# Venus_GPS_logger-sma.net
KiCad netlist of a schematic drawn in EAGLE
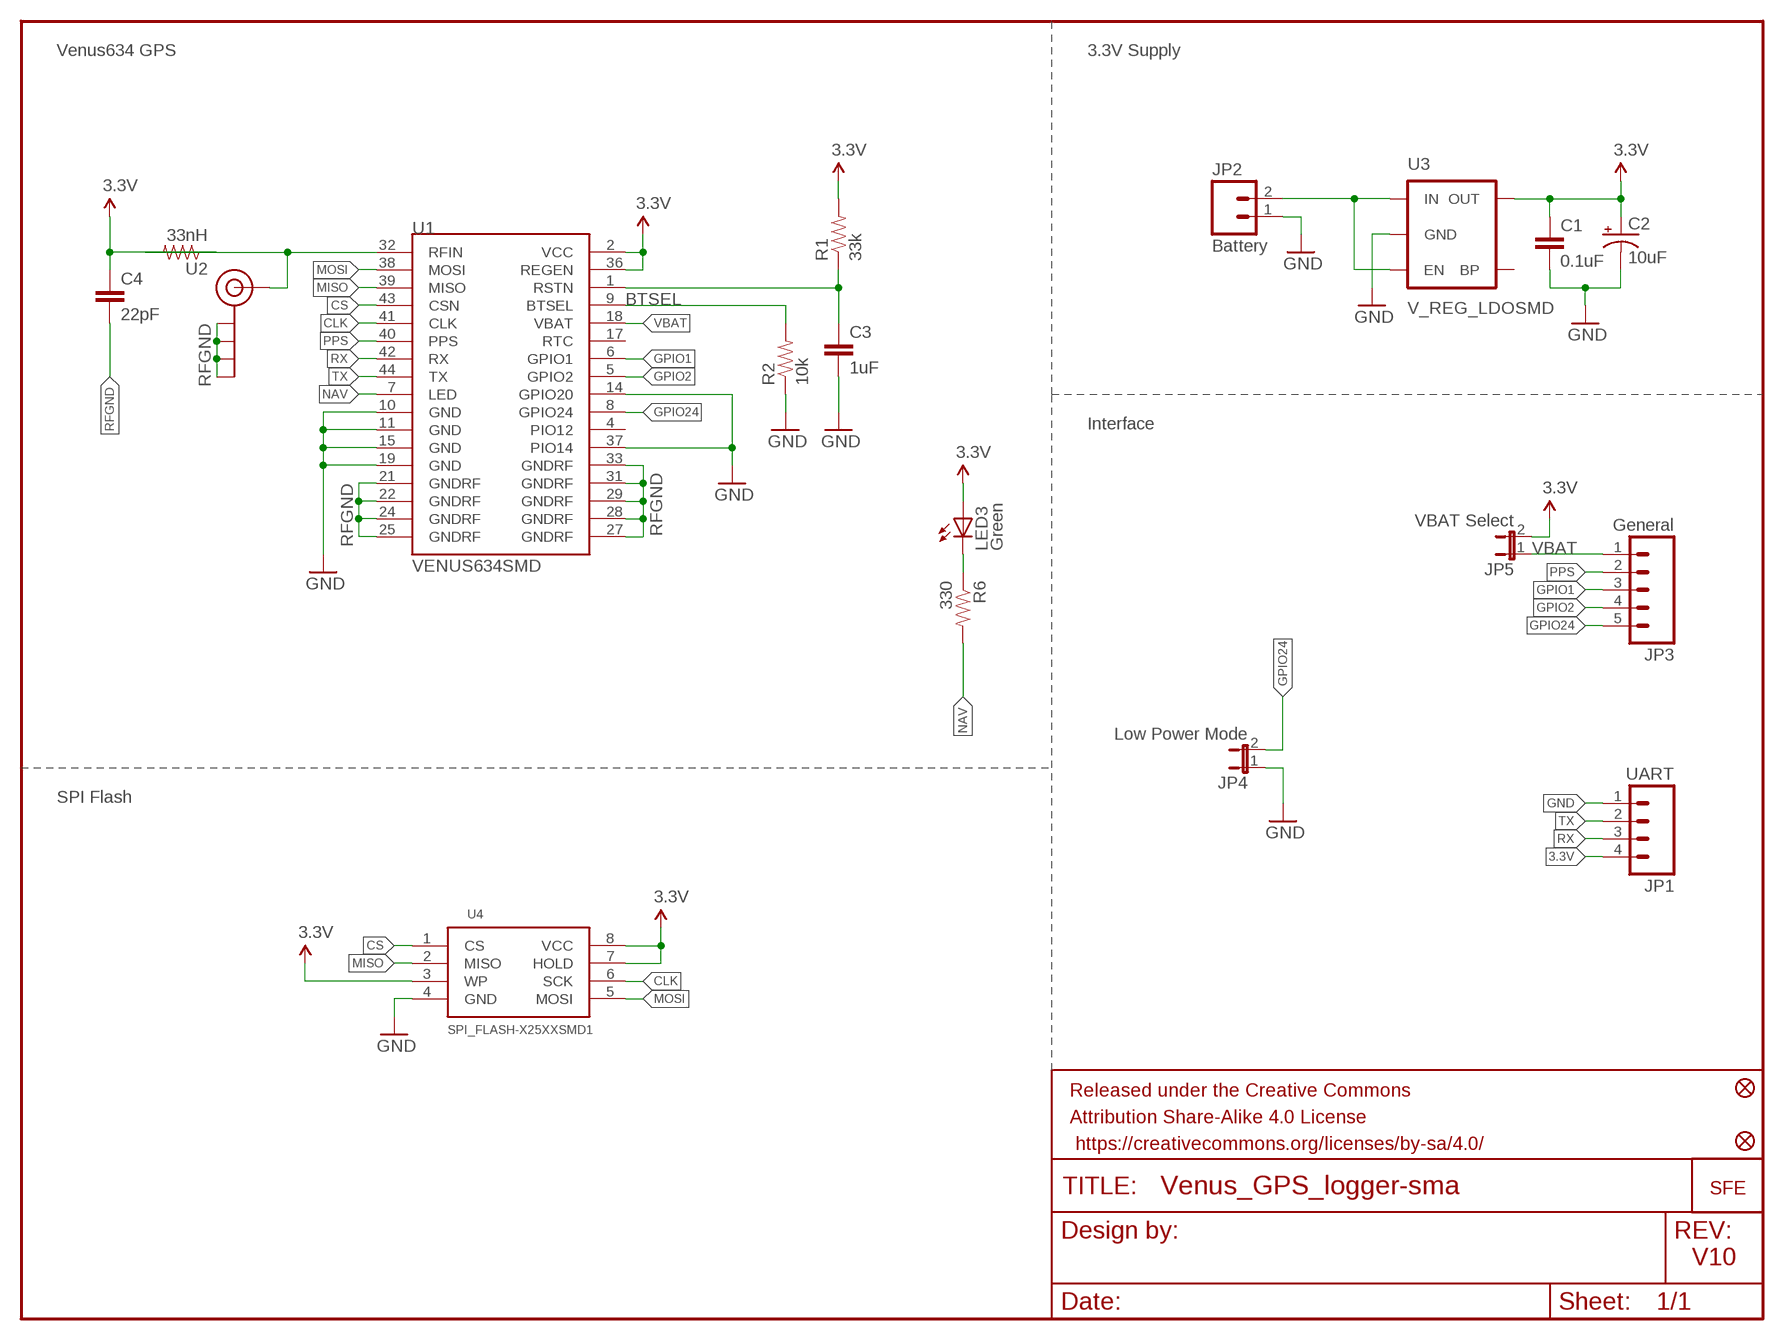
[diagram p0: schematic, sheet 1]

(export (version "E")
  (design (tool "Eeschema 10.0.6"))
  (components
    (comp (ref "C1")
      (value "0.1uF")
      (footprint "eagle-import:0603-CAP")
      (libsource (lib "eagle-import") (part "0.1UF-25V(+80/-20%)(0603)"))
    )
    (comp (ref "C2")
      (value "10uF")
      (footprint "eagle-import:EIA3216")
      (libsource (lib "eagle-import") (part "CAP_POL1206"))
    )
    (comp (ref "C3")
      (value "1uF")
      (footprint "eagle-import:0603-CAP")
      (libsource (lib "eagle-import") (part "1.0UF-16V-10%(0603)"))
    )
    (comp (ref "C4")
      (value "22pF")
      (footprint "eagle-import:0603-CAP")
      (libsource (lib "eagle-import") (part "22PF-50V-5%(0603)"))
    )
    (comp (ref "FID1")
      (value "FIDUCIAL1X2")
      (footprint "eagle-import:FIDUCIAL-1X2")
      (libsource (lib "eagle-import") (part "FIDUCIAL1X2"))
    )
    (comp (ref "FID2")
      (value "FIDUCIAL1X2")
      (footprint "eagle-import:FIDUCIAL-1X2")
      (libsource (lib "eagle-import") (part "FIDUCIAL1X2"))
    )
    (comp (ref "FRAME1")
      (value "FRAME-LETTER")
      (footprint "eagle-import:CREATIVE_COMMONS")
      (libsource (lib "eagle-import") (part "FRAME-LETTER"))
    )
    (comp (ref "J$1")
      (value "SMA_EDGE")
      (footprint "eagle-import:SMA-EDGE")
      (libsource (lib "eagle-import") (part "SMA_EDGE"))
    )
    (comp (ref "JP1")
      (value "UART")
      (footprint "eagle-import:1X04")
      (libsource (lib "eagle-import") (part "M04PTH"))
    )
    (comp (ref "JP2")
      (value "Battery")
      (footprint "eagle-import:S2B-PH")
      (libsource (lib "eagle-import") (part "M02-JST-2MM-SMT"))
    )
    (comp (ref "JP3")
      (value "General")
      (footprint "eagle-import:1X05")
      (libsource (lib "eagle-import") (part "M05PTH"))
    )
    (comp (ref "JP4")
      (value "Low Power Mode")
      (footprint "eagle-import:SJ_2S")
      (libsource (lib "eagle-import") (part "JUMPER-2SMD-NC"))
    )
    (comp (ref "JP5")
      (value "VBAT Select")
      (footprint "eagle-import:SJ_2S")
      (libsource (lib "eagle-import") (part "JUMPER-2SMD-NC"))
    )
    (comp (ref "LED3")
      (value "Green")
      (footprint "eagle-import:LED-0603")
      (libsource (lib "eagle-import") (part "LED-GREEN0603"))
    )
    (comp (ref "R1")
      (value "33k")
      (footprint "eagle-import:0603-RES")
      (libsource (lib "eagle-import") (part "33KOHM1/10W1%(0603)"))
    )
    (comp (ref "R2")
      (value "10k")
      (footprint "eagle-import:0603-RES")
      (libsource (lib "eagle-import") (part "10KOHM1/10W1%(0603)0603"))
    )
    (comp (ref "R6")
      (value "330")
      (footprint "eagle-import:0603-RES")
      (libsource (lib "eagle-import") (part "330OHM1/10W1%(0603)"))
    )
    (comp (ref "U$1")
      (value "LOGO-SFESK")
      (footprint "eagle-import:SFE-LOGO-FLAME")
      (libsource (lib "eagle-import") (part "LOGO-SFESK"))
    )
    (comp (ref "U1")
      (value "VENUS634SMD")
      (footprint "eagle-import:LGA44")
      (libsource (lib "eagle-import") (part "VENUS634SMD"))
    )
    (comp (ref "U2")
      (value "33nH")
      (footprint "eagle-import:0603-RES")
      (libsource (lib "eagle-import") (part "33NH"))
    )
    (comp (ref "U3")
      (value "V_REG_LDOSMD")
      (footprint "eagle-import:SOT23-5")
      (libsource (lib "eagle-import") (part "V_REG_LDOSMD"))
    )
    (comp (ref "U4")
      (value "SPI_FLASH-X25XXSMD1")
      (footprint "eagle-import:SO08-EIAJ")
      (libsource (lib "eagle-import") (part "SPI_FLASH-X25XXSMD1"))
    )
  )
  (nets
    (net (code "1") (name "/BTSEL") (class "Default")
      (node (ref "R2") (pin "2") (pinfunction "2_2") (pintype "passive"))
      (node (ref "U1") (pin "9") (pinfunction "BTSEL_9") (pintype "bidirectional"))
    )
    (net (code "2") (name "3.3V") (class "Default")
      (node (ref "C1") (pin "1") (pinfunction "1_1") (pintype "passive"))
      (node (ref "C2") (pin "A") (pinfunction "+_A") (pintype "passive"))
      (node (ref "C4") (pin "1") (pinfunction "1_1") (pintype "passive"))
      (node (ref "JP1") (pin "4") (pinfunction "4_4") (pintype "passive"))
      (node (ref "JP5") (pin "2") (pinfunction "2_2") (pintype "passive"))
      (node (ref "LED3") (pin "A") (pinfunction "A_A") (pintype "passive"))
      (node (ref "R1") (pin "2") (pinfunction "2_2") (pintype "passive"))
      (node (ref "U1") (pin "2") (pinfunction "VCC_2") (pintype "bidirectional"))
      (node (ref "U1") (pin "36") (pinfunction "REGEN_36") (pintype "bidirectional"))
      (node (ref "U2") (pin "1") (pinfunction "1_1") (pintype "passive"))
      (node (ref "U3") (pin "5") (pinfunction "OUT_5") (pintype "passive"))
      (node (ref "U4") (pin "3") (pinfunction "WP_3") (pintype "bidirectional"))
      (node (ref "U4") (pin "7") (pinfunction "HOLD_7") (pintype "bidirectional"))
      (node (ref "U4") (pin "8") (pinfunction "VCC_8") (pintype "bidirectional"))
    )
    (net (code "3") (name "CLK") (class "Default")
      (node (ref "U1") (pin "41") (pinfunction "CLK_41") (pintype "bidirectional"))
      (node (ref "U4") (pin "6") (pinfunction "SCK_6") (pintype "bidirectional"))
    )
    (net (code "4") (name "CS") (class "Default")
      (node (ref "U1") (pin "43") (pinfunction "CSN_43") (pintype "bidirectional"))
      (node (ref "U4") (pin "1") (pinfunction "CS_1") (pintype "bidirectional"))
    )
    (net (code "5") (name "GND") (class "Default")
      (node (ref "C1") (pin "2") (pinfunction "2_2") (pintype "passive"))
      (node (ref "C2") (pin "C") (pinfunction "-_C") (pintype "passive"))
      (node (ref "C3") (pin "2") (pinfunction "2_2") (pintype "passive"))
      (node (ref "JP1") (pin "1") (pinfunction "1_1") (pintype "passive"))
      (node (ref "JP2") (pin "1") (pinfunction "1_1") (pintype "passive"))
      (node (ref "JP4") (pin "1") (pinfunction "1_1") (pintype "passive"))
      (node (ref "R2") (pin "1") (pinfunction "1_1") (pintype "passive"))
      (node (ref "U1") (pin "10") (pinfunction "GND_10") (pintype "bidirectional"))
      (node (ref "U1") (pin "11") (pinfunction "GND_11") (pintype "bidirectional"))
      (node (ref "U1") (pin "14") (pinfunction "GPIO20_14") (pintype "bidirectional"))
      (node (ref "U1") (pin "15") (pinfunction "GND_15") (pintype "bidirectional"))
      (node (ref "U1") (pin "19") (pinfunction "GND_19") (pintype "bidirectional"))
      (node (ref "U1") (pin "37") (pinfunction "PIO14_37") (pintype "bidirectional"))
      (node (ref "U3") (pin "2") (pinfunction "GND_2") (pintype "input"))
      (node (ref "U4") (pin "4") (pinfunction "GND_4") (pintype "bidirectional"))
    )
    (net (code "6") (name "GPIO1") (class "Default")
      (node (ref "JP3") (pin "3") (pinfunction "3_3") (pintype "passive"))
      (node (ref "U1") (pin "6") (pinfunction "GPIO1_6") (pintype "bidirectional"))
    )
    (net (code "7") (name "GPIO2") (class "Default")
      (node (ref "JP3") (pin "4") (pinfunction "4_4") (pintype "passive"))
      (node (ref "U1") (pin "5") (pinfunction "GPIO2_5") (pintype "bidirectional"))
    )
    (net (code "8") (name "GPIO24") (class "Default")
      (node (ref "JP3") (pin "5") (pinfunction "5_5") (pintype "passive"))
      (node (ref "JP4") (pin "2") (pinfunction "2_2") (pintype "passive"))
      (node (ref "U1") (pin "8") (pinfunction "GPIO24_8") (pintype "bidirectional"))
    )
    (net (code "9") (name "MISO") (class "Default")
      (node (ref "U1") (pin "39") (pinfunction "MISO_39") (pintype "bidirectional"))
      (node (ref "U4") (pin "2") (pinfunction "MISO_2") (pintype "bidirectional"))
    )
    (net (code "10") (name "MOSI") (class "Default")
      (node (ref "U1") (pin "38") (pinfunction "MOSI_38") (pintype "bidirectional"))
      (node (ref "U4") (pin "5") (pinfunction "MOSI_5") (pintype "bidirectional"))
    )
    (net (code "11") (name "NAV") (class "Default")
      (node (ref "R6") (pin "2") (pinfunction "2_2") (pintype "passive"))
      (node (ref "U1") (pin "7") (pinfunction "LED_7") (pintype "bidirectional"))
    )
    (net (code "12") (name "Net-(J$1-SIGNAL)") (class "Default")
      (node (ref "J$1") (pin "SIG") (pinfunction "SIGNAL_SIG") (pintype "bidirectional"))
      (node (ref "U1") (pin "32") (pinfunction "RFIN_32") (pintype "bidirectional"))
      (node (ref "U2") (pin "2") (pinfunction "2_2") (pintype "passive"))
    )
    (net (code "13") (name "Net-(LED3-PadC)") (class "Default")
      (node (ref "LED3") (pin "C") (pinfunction "C_C") (pintype "passive"))
      (node (ref "R6") (pin "1") (pinfunction "1_1") (pintype "passive"))
    )
    (net (code "14") (name "Net-(U1-RSTN)") (class "Default")
      (node (ref "C3") (pin "1") (pinfunction "1_1") (pintype "passive"))
      (node (ref "R1") (pin "1") (pinfunction "1_1") (pintype "passive"))
      (node (ref "U1") (pin "1") (pinfunction "RSTN_1") (pintype "bidirectional"))
    )
    (net (code "15") (name "Net-(U3-EN)") (class "Default")
      (node (ref "JP2") (pin "2") (pinfunction "2_2") (pintype "passive"))
      (node (ref "U3") (pin "1") (pinfunction "IN_1") (pintype "input"))
      (node (ref "U3") (pin "3") (pinfunction "EN_3") (pintype "input"))
    )
    (net (code "16") (name "PPS") (class "Default")
      (node (ref "JP3") (pin "2") (pinfunction "2_2") (pintype "passive"))
      (node (ref "U1") (pin "40") (pinfunction "PPS_40") (pintype "bidirectional"))
    )
    (net (code "17") (name "RFGND") (class "Default")
      (node (ref "C4") (pin "2") (pinfunction "2_2") (pintype "passive"))
      (node (ref "J$1") (pin "GND@0") (pinfunction "GND_GND@0") (pintype "bidirectional"))
      (node (ref "J$1") (pin "GND@1") (pinfunction "GND_GND@1") (pintype "bidirectional"))
      (node (ref "J$1") (pin "GND@2") (pinfunction "GND_GND@2") (pintype "bidirectional"))
      (node (ref "J$1") (pin "GND@3") (pinfunction "GND_GND@3") (pintype "bidirectional"))
      (node (ref "U1") (pin "21") (pinfunction "GNDRF_21") (pintype "bidirectional"))
      (node (ref "U1") (pin "22") (pinfunction "GNDRF_22") (pintype "bidirectional"))
      (node (ref "U1") (pin "24") (pinfunction "GNDRF_24") (pintype "bidirectional"))
      (node (ref "U1") (pin "25") (pinfunction "GNDRF_25") (pintype "bidirectional"))
      (node (ref "U1") (pin "27") (pinfunction "GNDRF_27") (pintype "bidirectional"))
      (node (ref "U1") (pin "28") (pinfunction "GNDRF_28") (pintype "bidirectional"))
      (node (ref "U1") (pin "29") (pinfunction "GNDRF_29") (pintype "bidirectional"))
      (node (ref "U1") (pin "31") (pinfunction "GNDRF_31") (pintype "bidirectional"))
      (node (ref "U1") (pin "33") (pinfunction "GNDRF_33") (pintype "bidirectional"))
    )
    (net (code "18") (name "RX") (class "Default")
      (node (ref "JP1") (pin "3") (pinfunction "3_3") (pintype "passive"))
      (node (ref "U1") (pin "42") (pinfunction "RX_42") (pintype "bidirectional"))
    )
    (net (code "19") (name "TX") (class "Default")
      (node (ref "JP1") (pin "2") (pinfunction "2_2") (pintype "passive"))
      (node (ref "U1") (pin "44") (pinfunction "TX_44") (pintype "bidirectional"))
    )
    (net (code "20") (name "VBAT") (class "Default")
      (node (ref "JP3") (pin "1") (pinfunction "1_1") (pintype "passive"))
      (node (ref "JP5") (pin "1") (pinfunction "1_1") (pintype "passive"))
      (node (ref "U1") (pin "18") (pinfunction "VBAT_18") (pintype "bidirectional"))
    )
    (net (code "21") (name "unconnected-(U1-PIO12-Pad4)") (class "Default")
      (node (ref "U1") (pin "4") (pinfunction "PIO12_4") (pintype "bidirectional"))
    )
    (net (code "22") (name "unconnected-(U1-RTC-Pad17)") (class "Default")
      (node (ref "U1") (pin "17") (pinfunction "RTC_17") (pintype "bidirectional"))
    )
    (net (code "23") (name "unconnected-(U3-BP-Pad4)") (class "Default")
      (node (ref "U3") (pin "4") (pinfunction "BP_4") (pintype "input"))
    )
  )
)
